# SC_Integrador.net
KiCad netlist of a schematic drawn in Altium Designer
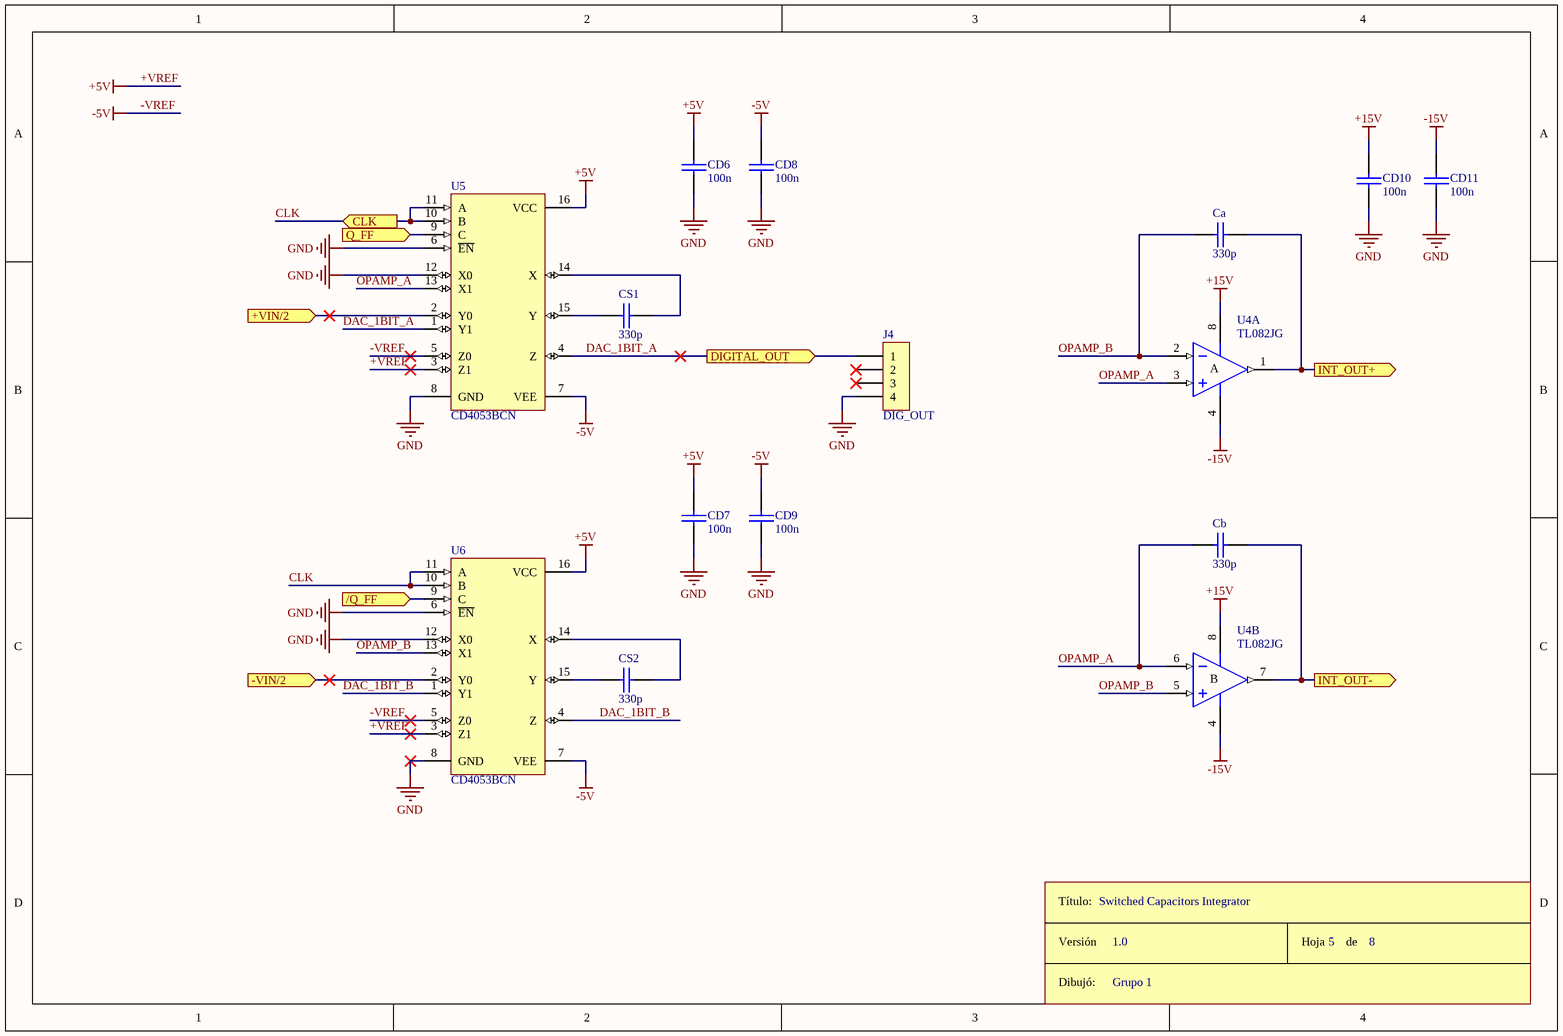
[diagram p0: SC_Integrador.SchDoc]

(export (version "E")
  (design (tool "Eeschema 10.0.6"))
  (components
    (comp (ref "Ca") (value "330p") (footprint "CAP100") (libsource (lib "LIBEBAL") (part "CAP")))
    (comp (ref "Cb") (value "330p") (footprint "CAP100") (libsource (lib "LIBEBAL") (part "CAP")))
    (comp (ref "CD6") (value "100n") (footprint "CAP100") (libsource (lib "LIBEBAL") (part "CAP")))
    (comp (ref "CD7") (value "100n") (footprint "CAP100") (libsource (lib "LIBEBAL") (part "CAP")))
    (comp (ref "CD8") (value "100n") (footprint "CAP100") (libsource (lib "LIBEBAL") (part "CAP")))
    (comp (ref "CD9") (value "100n") (footprint "CAP100") (libsource (lib "LIBEBAL") (part "CAP")))
    (comp (ref "CD10") (value "100n") (footprint "CAP100") (libsource (lib "LIBEBAL") (part "CAP")))
    (comp (ref "CD11") (value "100n") (footprint "CAP100") (libsource (lib "LIBEBAL") (part "CAP")))
    (comp (ref "CS1") (value "330p") (footprint "CAP100") (libsource (lib "LIBEBAL") (part "CAP")))
    (comp (ref "CS2") (value "330p") (footprint "CAP100") (libsource (lib "LIBEBAL") (part "CAP")))
    (comp (ref "J4") (value "DIG_OUT") (footprint "SIP4") (libsource (lib "LIBEBAL") (part "CON4")))
    (comp (ref "ROT4") (value "Rótulo") (libsource (lib "LIB PIO IX") (part "Rótulo")))
    (comp (ref "U4")
      (value "TL082JG")
      (footprint "JG008")
      (description "JFET-Input Operational Amplifier")
      (fields (field (name "PUBLISHER") "Altium Limited"))
      (libsource (lib "TI Operational Amplifier") (part "TL082JG"))
    )
    (comp (ref "U5")
      (value "CD4053BCN")
      (footprint "N16E")
      (description "Triple 2-Channnel Analog Multiplexer/Demutiplexer")
      (fields (field (name "PUBLISHER") "Altium Limited"))
      (libsource (lib "FSC Logic Multiplexer") (part "CD4053BCN"))
    )
    (comp (ref "U6")
      (value "CD4053BCN")
      (footprint "N16E")
      (description "Triple 2-Channnel Analog Multiplexer/Demutiplexer")
      (fields (field (name "PUBLISHER") "Altium Limited"))
      (libsource (lib "FSC Logic Multiplexer") (part "CD4053BCN"))
    )
  )
  (nets
    (net (code "1") (name "+5V") (class "Default")
      (node (ref "CD6") (pin "1") (pinfunction "1_1") (pintype "passive"))
      (node (ref "CD7") (pin "1") (pinfunction "1_1") (pintype "passive"))
      (node (ref "U5") (pin "16") (pinfunction "VCC_16") (pintype "power_in"))
      (node (ref "U5") (pin "3") (pinfunction "Z1_3") (pintype "bidirectional"))
      (node (ref "U6") (pin "16") (pinfunction "VCC_16") (pintype "power_in"))
      (node (ref "U6") (pin "3") (pinfunction "Z1_3") (pintype "bidirectional"))
    )
    (net (code "2") (name "+15V") (class "Default")
      (node (ref "CD10") (pin "1") (pinfunction "1_1") (pintype "passive"))
      (node (ref "U4") (pin "8") (pinfunction "V+_8") (pintype "power_in"))
    )
    (net (code "3") (name "-5V") (class "Default")
      (node (ref "CD8") (pin "1") (pinfunction "1_1") (pintype "passive"))
      (node (ref "CD9") (pin "1") (pinfunction "1_1") (pintype "passive"))
      (node (ref "U5") (pin "5") (pinfunction "Z0_5") (pintype "bidirectional"))
      (node (ref "U5") (pin "7") (pinfunction "VEE_7") (pintype "power_in"))
      (node (ref "U6") (pin "5") (pinfunction "Z0_5") (pintype "bidirectional"))
      (node (ref "U6") (pin "7") (pinfunction "VEE_7") (pintype "power_in"))
    )
    (net (code "4") (name "-15V") (class "Default")
      (node (ref "CD11") (pin "1") (pinfunction "1_1") (pintype "passive"))
      (node (ref "U4") (pin "4") (pinfunction "V-_4") (pintype "power_in"))
    )
    (net (code "5") (name "/+VIN{slash}2") (class "Default")
      (node (ref "U5") (pin "2") (pinfunction "Y0_2") (pintype "bidirectional+no_connect"))
    )
    (net (code "6") (name "/-VIN{slash}2") (class "Default")
      (node (ref "U6") (pin "2") (pinfunction "Y0_2") (pintype "bidirectional+no_connect"))
    )
    (net (code "7") (name "/CLK") (class "Default")
      (node (ref "U5") (pin "10") (pinfunction "B_10") (pintype "input"))
      (node (ref "U5") (pin "11") (pinfunction "A_11") (pintype "input"))
      (node (ref "U6") (pin "10") (pinfunction "B_10") (pintype "input"))
      (node (ref "U6") (pin "11") (pinfunction "A_11") (pintype "input"))
    )
    (net (code "8") (name "/DAC_1BIT_A") (class "Default")
      (node (ref "J4") (pin "1") (pinfunction "1_1") (pintype "passive"))
      (node (ref "U5") (pin "1") (pinfunction "Y1_1") (pintype "bidirectional"))
      (node (ref "U5") (pin "4") (pinfunction "Z_4") (pintype "bidirectional"))
    )
    (net (code "9") (name "/DAC_1BIT_B") (class "Default")
      (node (ref "U6") (pin "1") (pinfunction "Y1_1") (pintype "bidirectional"))
      (node (ref "U6") (pin "4") (pinfunction "Z_4") (pintype "bidirectional"))
    )
    (net (code "10") (name "/INT_OUT+") (class "Default")
      (node (ref "Ca") (pin "2") (pinfunction "2_2") (pintype "passive"))
      (node (ref "U4") (pin "1") (pinfunction "OUT_1") (pintype "output"))
    )
    (net (code "11") (name "/INT_OUT-") (class "Default")
      (node (ref "Cb") (pin "2") (pinfunction "2_2") (pintype "passive"))
      (node (ref "U4") (pin "7") (pinfunction "OUT_7") (pintype "output"))
    )
    (net (code "12") (name "/OPAMP_A") (class "Default")
      (node (ref "Cb") (pin "1") (pinfunction "1_1") (pintype "passive"))
      (node (ref "U4") (pin "3") (pinfunction "IN+_3") (pintype "input"))
      (node (ref "U4") (pin "6") (pinfunction "IN-_6") (pintype "input"))
      (node (ref "U5") (pin "13") (pinfunction "X1_13") (pintype "bidirectional"))
    )
    (net (code "13") (name "/OPAMP_B") (class "Default")
      (node (ref "Ca") (pin "1") (pinfunction "1_1") (pintype "passive"))
      (node (ref "U4") (pin "2") (pinfunction "IN-_2") (pintype "input"))
      (node (ref "U4") (pin "5") (pinfunction "IN+_5") (pintype "input"))
      (node (ref "U6") (pin "13") (pinfunction "X1_13") (pintype "bidirectional"))
    )
    (net (code "14") (name "/Q_FF") (class "Default")
      (node (ref "U5") (pin "9") (pinfunction "C_9") (pintype "input"))
    )
    (net (code "15") (name "/{slash}Q_FF") (class "Default")
      (node (ref "U6") (pin "9") (pinfunction "C_9") (pintype "input"))
    )
    (net (code "16") (name "GND") (class "Default")
      (node (ref "CD10") (pin "2") (pinfunction "2_2") (pintype "passive"))
      (node (ref "CD11") (pin "2") (pinfunction "2_2") (pintype "passive"))
      (node (ref "CD6") (pin "2") (pinfunction "2_2") (pintype "passive"))
      (node (ref "CD7") (pin "2") (pinfunction "2_2") (pintype "passive"))
      (node (ref "CD8") (pin "2") (pinfunction "2_2") (pintype "passive"))
      (node (ref "CD9") (pin "2") (pinfunction "2_2") (pintype "passive"))
      (node (ref "J4") (pin "4") (pinfunction "4_4") (pintype "passive"))
      (node (ref "U5") (pin "12") (pinfunction "X0_12") (pintype "bidirectional"))
      (node (ref "U5") (pin "6") (pinfunction "~{EN}_6") (pintype "input"))
      (node (ref "U5") (pin "8") (pinfunction "GND_8") (pintype "power_in"))
      (node (ref "U6") (pin "12") (pinfunction "X0_12") (pintype "bidirectional"))
      (node (ref "U6") (pin "6") (pinfunction "~{EN}_6") (pintype "input"))
      (node (ref "U6") (pin "8") (pinfunction "GND_8") (pintype "power_in"))
    )
    (net (code "17") (name "Net-(U5-X)") (class "Default")
      (node (ref "CS1") (pin "1") (pinfunction "1_1") (pintype "passive"))
      (node (ref "U5") (pin "14") (pinfunction "X_14") (pintype "bidirectional"))
    )
    (net (code "18") (name "Net-(U5-Y)") (class "Default")
      (node (ref "CS1") (pin "2") (pinfunction "2_2") (pintype "passive"))
      (node (ref "U5") (pin "15") (pinfunction "Y_15") (pintype "bidirectional"))
    )
    (net (code "19") (name "Net-(U6-X)") (class "Default")
      (node (ref "CS2") (pin "2") (pinfunction "2_2") (pintype "passive"))
      (node (ref "U6") (pin "14") (pinfunction "X_14") (pintype "bidirectional"))
    )
    (net (code "20") (name "Net-(U6-Y)") (class "Default")
      (node (ref "CS2") (pin "1") (pinfunction "1_1") (pintype "passive"))
      (node (ref "U6") (pin "15") (pinfunction "Y_15") (pintype "bidirectional"))
    )
    (net (code "21") (name "unconnected-(J4-Pad2)") (class "Default")
      (node (ref "J4") (pin "2") (pinfunction "2_2") (pintype "passive+no_connect"))
    )
    (net (code "22") (name "unconnected-(J4-Pad3)") (class "Default")
      (node (ref "J4") (pin "3") (pinfunction "3_3") (pintype "passive+no_connect"))
    )
  )
)
